# APP_1_JTAG_m.net
KiCad netlist of a schematic drawn in Altium Designer
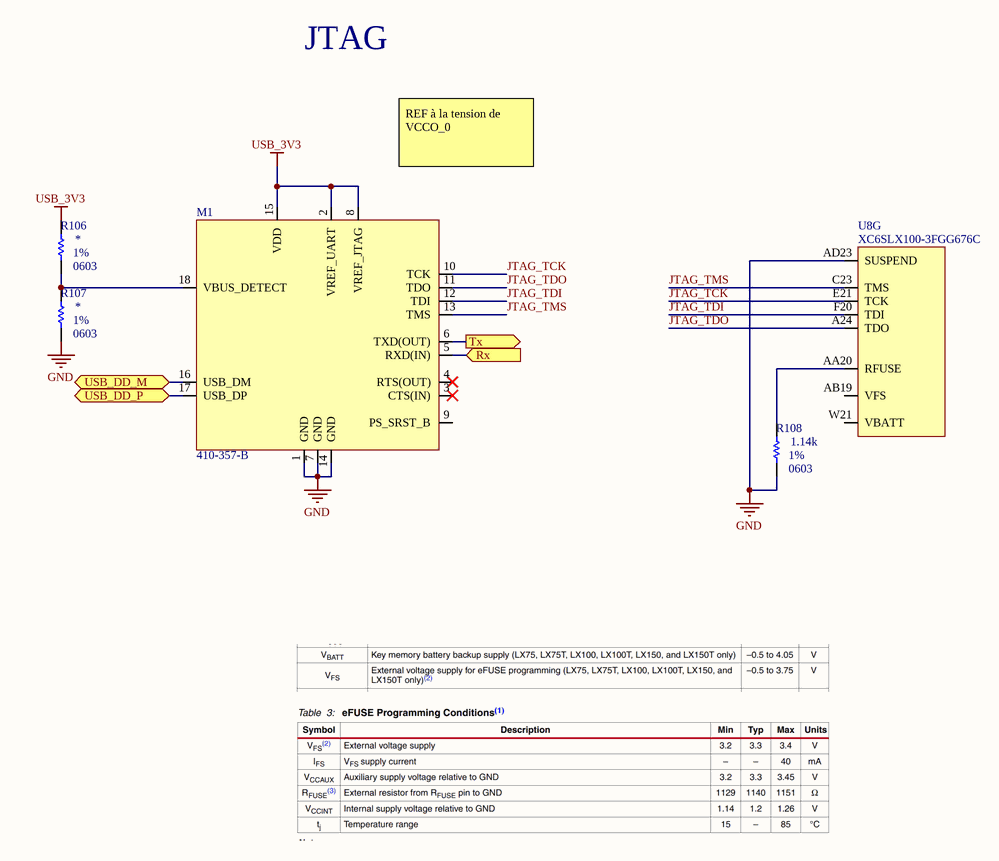
[diagram p0: APP_1_JTAG_m.SchDoc]

(export (version "E")
  (design (tool "Eeschema 10.0.6"))
  (components
    (comp (ref "M1")
      (value "410-357-B")
      (footprint "MOD_JTAG_410-357-B")
      (description "MOD - JTAG-SMT3-NC Programming Module For Xilinx FPGA - 18-SMT")
      (fields
        (field (name "CREATEDBY/DATE") "Tommy Rossignol 2018-11-23")
        (field (name "VERIFIEDBY") "Nicolas V. (2019-01-28)")
      )
      (libsource (lib "S7CAS_LIB2023") (part "MOD_JTAG_410-357-B"))
    )
    (comp (ref "R106")
      (value "RES - 0603")
      (footprint "RES_0603")
      (fields
        (field (name "PACKAGE") "0603")
        (field (name "PRECISION") "1%")
        (field (name "ALTIUM_VALUE") "*")
        (field (name "CREATEDBY") "Jonathan Bouchard")
      )
      (libsource (lib "S7CAS_LIB2023") (part "RES - 0603"))
    )
    (comp (ref "R107")
      (value "RES - 0603")
      (footprint "RES_0603")
      (fields
        (field (name "PACKAGE") "0603")
        (field (name "PRECISION") "1%")
        (field (name "ALTIUM_VALUE") "*")
        (field (name "CREATEDBY") "Jonathan Bouchard")
      )
      (libsource (lib "S7CAS_LIB2023") (part "RES - 0603"))
    )
    (comp (ref "R108")
      (value "1.14k")
      (footprint "RES_0603")
      (description "RES - 0603")
      (fields
        (field (name "PACKAGE") "0603")
        (field (name "PRECISION") "1%")
        (field (name "CREATEDBY") "Jonathan Bouchard")
      )
      (libsource (lib "S7CAS_LIB2023") (part "RES - 0603"))
    )
    (comp (ref "U8")
      (value "XC6SLX100-3FGG676C")
      (footprint "FPGA_XILINX_FGG676")
      (description "FPGA - XILINX SPARTAN 6 480 I/O - BGA-676")
      (fields
        (field (name "VOLTAGE") "1.14 V ~ 1.26 V")
        (field (name "MFG") "Xilinx")
        (field (name "CREATEDBY") "Jonathan Bouchard")
      )
      (libsource (lib "S7CAS_LIB2023") (part "FPGA_XC6SLX100-3FGG676C"))
    )
  )
  (nets
    (net (code "1") (name "/JTAG_TCK") (class "Default")
      (node (ref "M1") (pin "10") (pinfunction "TCK_10") (pintype "passive"))
      (node (ref "U8") (pin "E21") (pinfunction "TCK_E21") (pintype "passive"))
    )
    (net (code "2") (name "/JTAG_TDI") (class "Default")
      (node (ref "M1") (pin "12") (pinfunction "TDI_12") (pintype "passive"))
      (node (ref "U8") (pin "F20") (pinfunction "TDI_F20") (pintype "passive"))
    )
    (net (code "3") (name "/JTAG_TDO") (class "Default")
      (node (ref "M1") (pin "11") (pinfunction "TDO_11") (pintype "passive"))
      (node (ref "U8") (pin "A24") (pinfunction "TDO_A24") (pintype "passive"))
    )
    (net (code "4") (name "/JTAG_TMS") (class "Default")
      (node (ref "M1") (pin "13") (pinfunction "TMS_13") (pintype "passive"))
      (node (ref "U8") (pin "C23") (pinfunction "TMS_C23") (pintype "passive"))
    )
    (net (code "5") (name "/Rx") (class "Default")
      (node (ref "M1") (pin "5") (pinfunction "RXD(IN)_5") (pintype "passive"))
    )
    (net (code "6") (name "/Tx") (class "Default")
      (node (ref "M1") (pin "6") (pinfunction "TXD(OUT)_6") (pintype "passive"))
    )
    (net (code "7") (name "/USB_DD_M") (class "Default")
      (node (ref "M1") (pin "16") (pinfunction "USB_DM_16") (pintype "passive"))
    )
    (net (code "8") (name "/USB_DD_P") (class "Default")
      (node (ref "M1") (pin "17") (pinfunction "USB_DP_17") (pintype "passive"))
    )
    (net (code "9") (name "GND") (class "Default")
      (node (ref "M1") (pin "1") (pinfunction "GND_1") (pintype "passive"))
      (node (ref "M1") (pin "14") (pinfunction "GND_14") (pintype "passive"))
      (node (ref "M1") (pin "7") (pinfunction "GND_7") (pintype "passive"))
      (node (ref "R107") (pin "1") (pinfunction "1_1") (pintype "passive"))
      (node (ref "R108") (pin "1") (pinfunction "1_1") (pintype "passive"))
      (node (ref "U8") (pin "AD23") (pinfunction "SUSPEND_AD23") (pintype "passive"))
    )
    (net (code "10") (name "Net-(M1-VBUS_DETECT)") (class "Default")
      (node (ref "M1") (pin "18") (pinfunction "VBUS_DETECT_18") (pintype "passive"))
      (node (ref "R106") (pin "1") (pinfunction "1_1") (pintype "passive"))
      (node (ref "R107") (pin "2") (pinfunction "2_2") (pintype "passive"))
    )
    (net (code "11") (name "Net-(U8G-RFUSE)") (class "Default")
      (node (ref "R108") (pin "2") (pinfunction "2_2") (pintype "passive"))
      (node (ref "U8") (pin "AA20") (pinfunction "RFUSE_AA20") (pintype "passive"))
    )
    (net (code "12") (name "USB_3V3") (class "Default")
      (node (ref "M1") (pin "15") (pinfunction "VDD_15") (pintype "passive"))
      (node (ref "M1") (pin "2") (pinfunction "VREF_UART_2") (pintype "passive"))
      (node (ref "M1") (pin "8") (pinfunction "VREF_JTAG_8") (pintype "passive"))
      (node (ref "R106") (pin "2") (pinfunction "2_2") (pintype "passive"))
    )
    (net (code "13") (name "unconnected-(M1-CTS(IN)-Pad3)") (class "Default")
      (node (ref "M1") (pin "3") (pinfunction "CTS(IN)_3") (pintype "passive+no_connect"))
    )
    (net (code "14") (name "unconnected-(M1-PS_SRST_B-Pad9)") (class "Default")
      (node (ref "M1") (pin "9") (pinfunction "PS_SRST_B_9") (pintype "passive"))
    )
    (net (code "15") (name "unconnected-(M1-RTS(OUT)-Pad4)") (class "Default")
      (node (ref "M1") (pin "4") (pinfunction "RTS(OUT)_4") (pintype "passive+no_connect"))
    )
    (net (code "16") (name "unconnected-(U8G-VBATT-PadW21)") (class "Default")
      (node (ref "U8") (pin "W21") (pinfunction "VBATT_W21") (pintype "passive"))
    )
    (net (code "17") (name "unconnected-(U8G-VFS-PadAB19)") (class "Default")
      (node (ref "U8") (pin "AB19") (pinfunction "VFS_AB19") (pintype "passive"))
    )
  )
)
